# BioSignalPi-VersionA.net
KiCad netlist of a schematic drawn in EAGLE
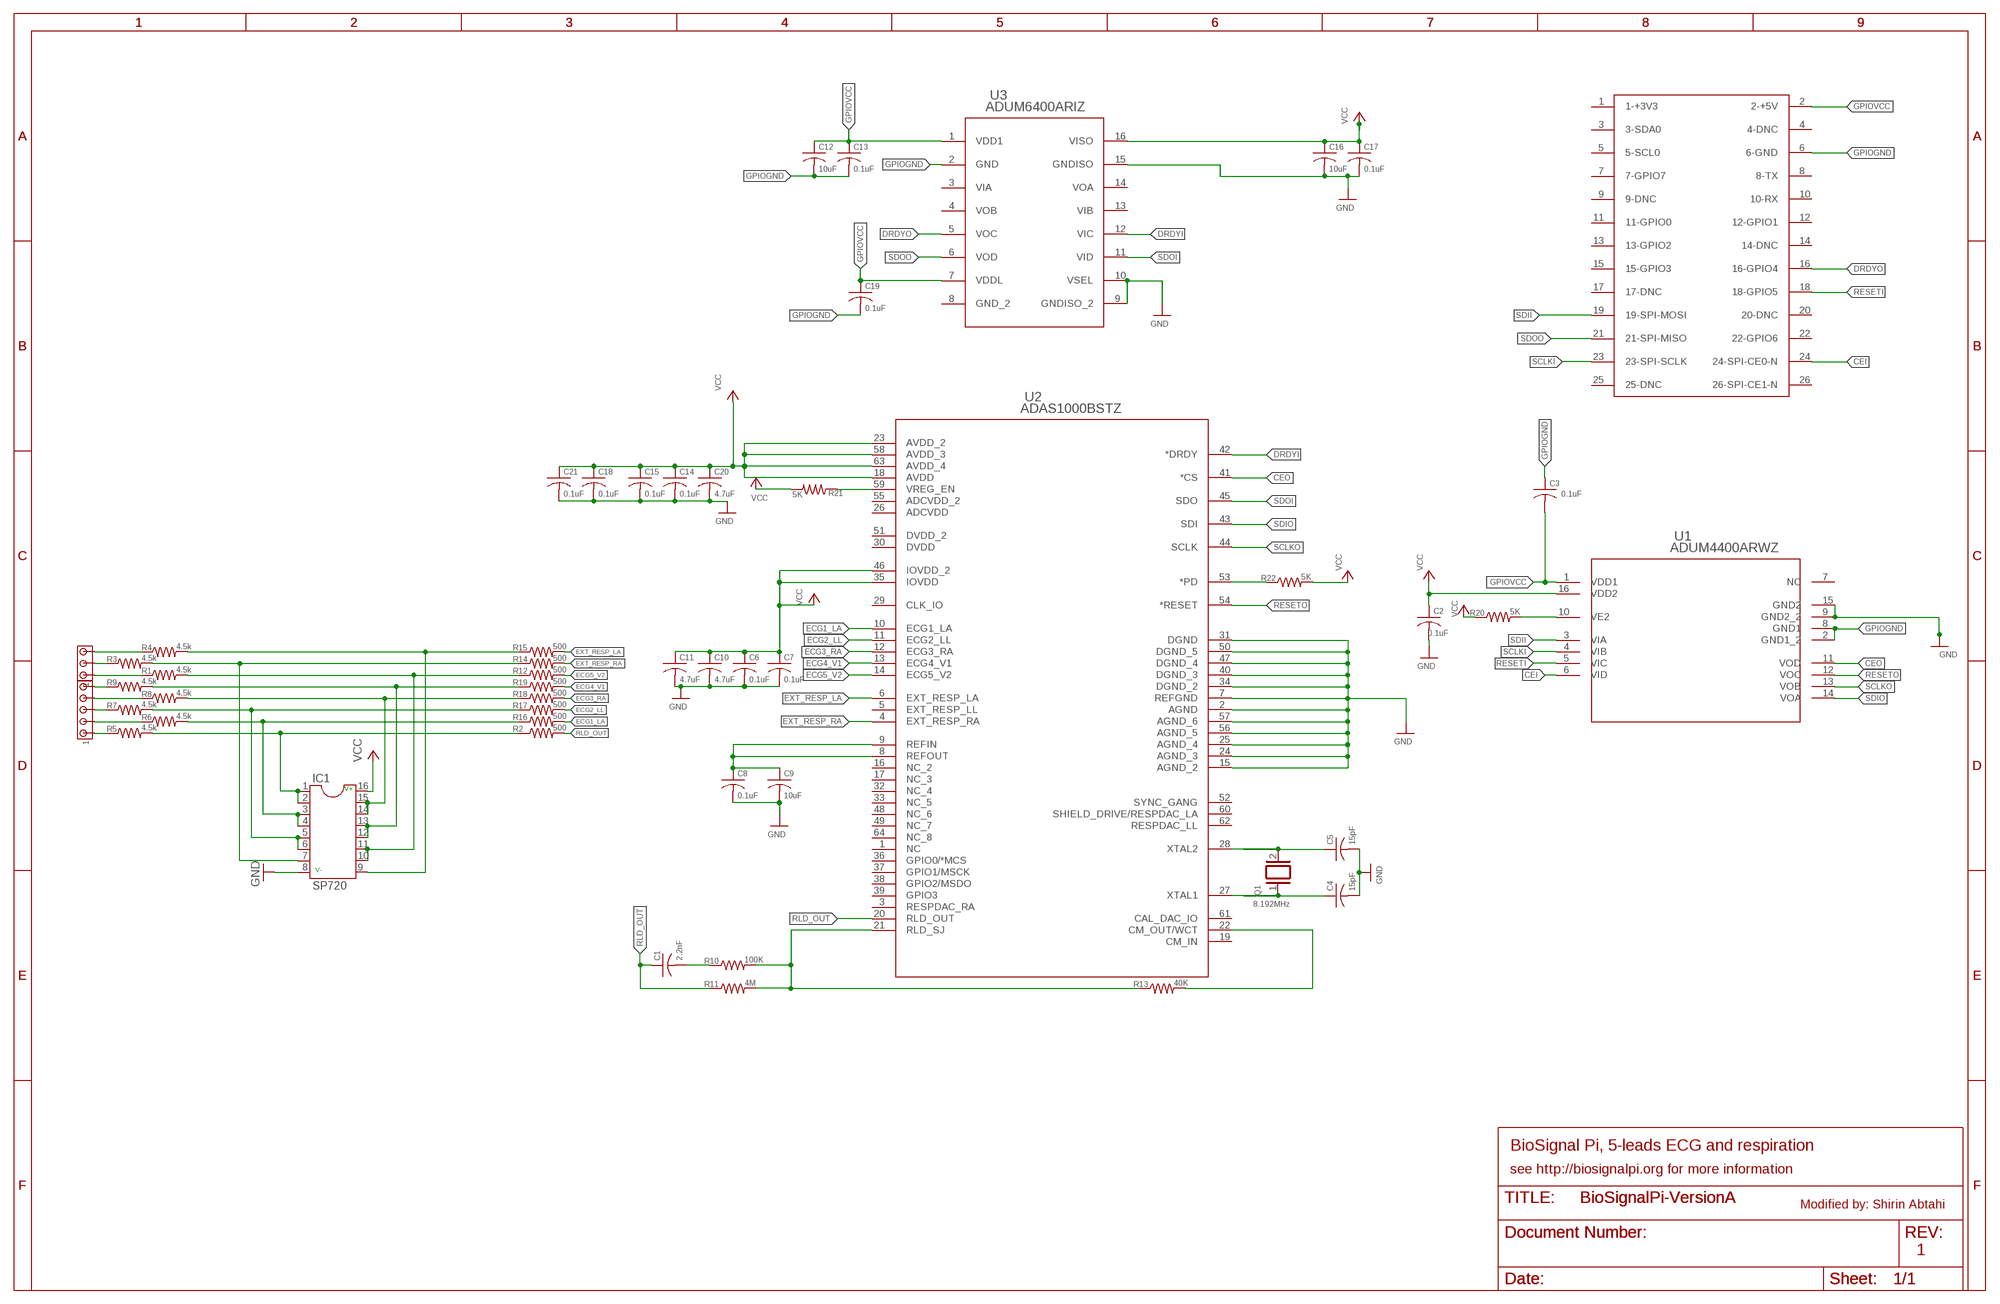
[diagram p0: schematic, sheet 1]

(export (version "E")
  (design (tool "Eeschema 10.0.6"))
  (components
    (comp (ref "C1")
      (value "2.2nF")
      (footprint "eagle-import:C0805")
      (libsource (lib "eagle-import") (part "C-USC0805"))
    )
    (comp (ref "C2")
      (value "0.1uF")
      (footprint "eagle-import:C0805")
      (libsource (lib "eagle-import") (part "C-USC0805"))
    )
    (comp (ref "C3")
      (value "0.1uF")
      (footprint "eagle-import:C0805")
      (libsource (lib "eagle-import") (part "C-USC0805"))
    )
    (comp (ref "C4")
      (value "15pF")
      (footprint "eagle-import:C0805")
      (libsource (lib "eagle-import") (part "C-USC0805"))
    )
    (comp (ref "C5")
      (value "15pF")
      (footprint "eagle-import:C0805")
      (libsource (lib "eagle-import") (part "C-USC0805"))
    )
    (comp (ref "C6")
      (value "0.1uF")
      (footprint "eagle-import:C0805")
      (libsource (lib "eagle-import") (part "C-USC0805"))
    )
    (comp (ref "C7")
      (value "0.1uF")
      (footprint "eagle-import:C0805")
      (libsource (lib "eagle-import") (part "C-USC0805"))
    )
    (comp (ref "C8")
      (value "0.1uF")
      (footprint "eagle-import:C0805")
      (libsource (lib "eagle-import") (part "C-USC0805"))
    )
    (comp (ref "C9")
      (value "10uF")
      (footprint "eagle-import:C0805")
      (libsource (lib "eagle-import") (part "C-USC0805"))
    )
    (comp (ref "C10")
      (value "4.7uF")
      (footprint "eagle-import:C0805")
      (libsource (lib "eagle-import") (part "C-USC0805"))
    )
    (comp (ref "C11")
      (value "4.7uF")
      (footprint "eagle-import:C0805")
      (libsource (lib "eagle-import") (part "C-USC0805"))
    )
    (comp (ref "C12")
      (value "10uF")
      (footprint "eagle-import:C0805")
      (libsource (lib "eagle-import") (part "C-USC0805"))
    )
    (comp (ref "C13")
      (value "0.1uF")
      (footprint "eagle-import:C0805")
      (libsource (lib "eagle-import") (part "C-USC0805"))
    )
    (comp (ref "C14")
      (value "0.1uF")
      (footprint "eagle-import:C0805")
      (libsource (lib "eagle-import") (part "C-USC0805"))
    )
    (comp (ref "C15")
      (value "0.1uF")
      (footprint "eagle-import:C0805")
      (libsource (lib "eagle-import") (part "C-USC0805"))
    )
    (comp (ref "C16")
      (value "10uF")
      (footprint "eagle-import:C0805")
      (libsource (lib "eagle-import") (part "C-USC0805"))
    )
    (comp (ref "C17")
      (value "0.1uF")
      (footprint "eagle-import:C0805")
      (libsource (lib "eagle-import") (part "C-USC0805"))
    )
    (comp (ref "C18")
      (value "0.1uF")
      (footprint "eagle-import:C0805")
      (libsource (lib "eagle-import") (part "C-USC0805"))
    )
    (comp (ref "C19")
      (value "0.1uF")
      (footprint "eagle-import:C0805")
      (libsource (lib "eagle-import") (part "C-USC0805"))
    )
    (comp (ref "C20")
      (value "4.7uF")
      (footprint "eagle-import:C0805")
      (libsource (lib "eagle-import") (part "C-USC0805"))
    )
    (comp (ref "C21")
      (value "0.1uF")
      (footprint "eagle-import:C0805")
      (libsource (lib "eagle-import") (part "C-USC0805"))
    )
    (comp (ref "IC1")
      (value "SP720")
      (footprint "eagle-import:DIL16")
      (libsource (lib "eagle-import") (part "DIL16"))
    )
    (comp (ref "J1")
      (value "JUMPERS")
      (footprint "eagle-import:10X03MTA")
      (libsource (lib "eagle-import") (part "MTA03-100"))
    )
    (comp (ref "J2")
      (value "JUMPERS")
      (footprint "eagle-import:10X05MTA")
      (libsource (lib "eagle-import") (part "MTA05-100"))
    )
    (comp (ref "Q1")
      (value "8.192MHz")
      (footprint "eagle-import:QS")
      (libsource (lib "eagle-import") (part "XTAL/S"))
    )
    (comp (ref "R1")
      (value "4.5k")
      (footprint "eagle-import:R0805")
      (libsource (lib "eagle-import") (part "R-US_R0805"))
    )
    (comp (ref "R2")
      (value "500")
      (footprint "eagle-import:R0805")
      (libsource (lib "eagle-import") (part "R-US_R0805"))
    )
    (comp (ref "R3")
      (value "4.5k")
      (footprint "eagle-import:R0805")
      (libsource (lib "eagle-import") (part "R-US_R0805"))
    )
    (comp (ref "R4")
      (value "4.5k")
      (footprint "eagle-import:R0805")
      (libsource (lib "eagle-import") (part "R-US_R0805"))
    )
    (comp (ref "R5")
      (value "4.5k")
      (footprint "eagle-import:R0805")
      (libsource (lib "eagle-import") (part "R-US_R0805"))
    )
    (comp (ref "R6")
      (value "4.5k")
      (footprint "eagle-import:R0805")
      (libsource (lib "eagle-import") (part "R-US_R0805"))
    )
    (comp (ref "R7")
      (value "4.5k")
      (footprint "eagle-import:R0805")
      (libsource (lib "eagle-import") (part "R-US_R0805"))
    )
    (comp (ref "R8")
      (value "4.5k")
      (footprint "eagle-import:R0805")
      (libsource (lib "eagle-import") (part "R-US_R0805"))
    )
    (comp (ref "R9")
      (value "4.5k")
      (footprint "eagle-import:R0805")
      (libsource (lib "eagle-import") (part "R-US_R0805"))
    )
    (comp (ref "R10")
      (value "100K")
      (footprint "eagle-import:R0805")
      (libsource (lib "eagle-import") (part "R-US_R0805"))
    )
    (comp (ref "R11")
      (value "4M")
      (footprint "eagle-import:R0805")
      (libsource (lib "eagle-import") (part "R-US_R0805"))
    )
    (comp (ref "R12")
      (value "500")
      (footprint "eagle-import:R0805")
      (libsource (lib "eagle-import") (part "R-US_R0805"))
    )
    (comp (ref "R13")
      (value "40K")
      (footprint "eagle-import:R0805")
      (libsource (lib "eagle-import") (part "R-US_R0805"))
    )
    (comp (ref "R14")
      (value "500")
      (footprint "eagle-import:R0805")
      (libsource (lib "eagle-import") (part "R-US_R0805"))
    )
    (comp (ref "R15")
      (value "500")
      (footprint "eagle-import:R0805")
      (libsource (lib "eagle-import") (part "R-US_R0805"))
    )
    (comp (ref "R16")
      (value "500")
      (footprint "eagle-import:R0805")
      (libsource (lib "eagle-import") (part "R-US_R0805"))
    )
    (comp (ref "R17")
      (value "500")
      (footprint "eagle-import:R0805")
      (libsource (lib "eagle-import") (part "R-US_R0805"))
    )
    (comp (ref "R18")
      (value "500")
      (footprint "eagle-import:R0805")
      (libsource (lib "eagle-import") (part "R-US_R0805"))
    )
    (comp (ref "R19")
      (value "500")
      (footprint "eagle-import:R0805")
      (libsource (lib "eagle-import") (part "R-US_R0805"))
    )
    (comp (ref "R20")
      (value "5K")
      (footprint "eagle-import:R0805")
      (libsource (lib "eagle-import") (part "R-US_R0805"))
    )
    (comp (ref "R21")
      (value "5K")
      (footprint "eagle-import:R0805")
      (libsource (lib "eagle-import") (part "R-US_R0805"))
    )
    (comp (ref "R22")
      (value "5K")
      (footprint "eagle-import:R0805")
      (libsource (lib "eagle-import") (part "R-US_R0805"))
    )
    (comp (ref "U$1")
      (value "RASPBERRY-PI")
      (footprint "eagle-import:RASPBERRY-PI")
      (libsource (lib "eagle-import") (part "RASPBERRY-PI"))
    )
    (comp (ref "U1")
      (value "ADUM4400ARWZ")
      (footprint "eagle-import:RW_16")
      (libsource (lib "eagle-import") (part "ADUM4400ARWZ"))
    )
    (comp (ref "U2")
      (value "ADAS1000BSTZ")
      (footprint "eagle-import:ST_64_2")
      (libsource (lib "eagle-import") (part "ADAS1000BSTZ"))
    )
    (comp (ref "U3")
      (value "ADUM6400ARIZ")
      (footprint "eagle-import:RI_16_1")
      (libsource (lib "eagle-import") (part "ADUM6400ARIZ"))
    )
  )
  (nets
    (net (code "1") (name "CEI") (class "Default")
      (node (ref "U$1") (pin "24") (pinfunction "24-SPI-CE0-N_24") (pintype "bidirectional"))
      (node (ref "U1") (pin "6") (pinfunction "VID_6") (pintype "passive"))
    )
    (net (code "2") (name "CEO") (class "Default")
      (node (ref "U1") (pin "11") (pinfunction "VOD_11") (pintype "passive"))
      (node (ref "U2") (pin "41") (pinfunction "*CS_41") (pintype "passive"))
    )
    (net (code "3") (name "DRDYI") (class "Default")
      (node (ref "U2") (pin "42") (pinfunction "*DRDY_42") (pintype "passive"))
      (node (ref "U3") (pin "12") (pinfunction "VIC_12") (pintype "passive"))
    )
    (net (code "4") (name "DRDYO") (class "Default")
      (node (ref "U$1") (pin "16") (pinfunction "16-GPIO4_16") (pintype "bidirectional"))
      (node (ref "U3") (pin "5") (pinfunction "VOC_5") (pintype "passive"))
    )
    (net (code "5") (name "ECG1_LA") (class "Default")
      (node (ref "R16") (pin "2") (pinfunction "2_2") (pintype "passive"))
      (node (ref "U2") (pin "10") (pinfunction "ECG1_LA_10") (pintype "passive"))
    )
    (net (code "6") (name "ECG2_LL") (class "Default")
      (node (ref "R17") (pin "2") (pinfunction "2_2") (pintype "passive"))
      (node (ref "U2") (pin "11") (pinfunction "ECG2_LL_11") (pintype "passive"))
    )
    (net (code "7") (name "ECG3_RA") (class "Default")
      (node (ref "R18") (pin "2") (pinfunction "2_2") (pintype "passive"))
      (node (ref "U2") (pin "12") (pinfunction "ECG3_RA_12") (pintype "passive"))
    )
    (net (code "8") (name "ECG4_V1") (class "Default")
      (node (ref "R19") (pin "2") (pinfunction "2_2") (pintype "passive"))
      (node (ref "U2") (pin "13") (pinfunction "ECG4_V1_13") (pintype "passive"))
    )
    (net (code "9") (name "ECG5_V2") (class "Default")
      (node (ref "R12") (pin "2") (pinfunction "2_2") (pintype "passive"))
      (node (ref "U2") (pin "14") (pinfunction "ECG5_V2_14") (pintype "passive"))
    )
    (net (code "10") (name "EXT_RESP_LA") (class "Default")
      (node (ref "R15") (pin "2") (pinfunction "2_2") (pintype "passive"))
      (node (ref "U2") (pin "6") (pinfunction "EXT_RESP_LA_6") (pintype "passive"))
    )
    (net (code "11") (name "EXT_RESP_RA") (class "Default")
      (node (ref "R14") (pin "2") (pinfunction "2_2") (pintype "passive"))
      (node (ref "U2") (pin "4") (pinfunction "EXT_RESP_RA_4") (pintype "passive"))
    )
    (net (code "12") (name "GND") (class "Default")
      (node (ref "C10") (pin "2") (pinfunction "2_2") (pintype "passive"))
      (node (ref "C11") (pin "2") (pinfunction "2_2") (pintype "passive"))
      (node (ref "C14") (pin "2") (pinfunction "2_2") (pintype "passive"))
      (node (ref "C15") (pin "2") (pinfunction "2_2") (pintype "passive"))
      (node (ref "C16") (pin "2") (pinfunction "2_2") (pintype "passive"))
      (node (ref "C17") (pin "2") (pinfunction "2_2") (pintype "passive"))
      (node (ref "C18") (pin "2") (pinfunction "2_2") (pintype "passive"))
      (node (ref "C2") (pin "2") (pinfunction "2_2") (pintype "passive"))
      (node (ref "C20") (pin "2") (pinfunction "2_2") (pintype "passive"))
      (node (ref "C21") (pin "2") (pinfunction "2_2") (pintype "passive"))
      (node (ref "C4") (pin "2") (pinfunction "2_2") (pintype "passive"))
      (node (ref "C5") (pin "2") (pinfunction "2_2") (pintype "passive"))
      (node (ref "C6") (pin "2") (pinfunction "2_2") (pintype "passive"))
      (node (ref "C7") (pin "2") (pinfunction "2_2") (pintype "passive"))
      (node (ref "C8") (pin "2") (pinfunction "2_2") (pintype "passive"))
      (node (ref "C9") (pin "2") (pinfunction "2_2") (pintype "passive"))
      (node (ref "IC1") (pin "8") (pinfunction "8_8") (pintype "passive"))
      (node (ref "U1") (pin "15") (pinfunction "GND2_15") (pintype "passive"))
      (node (ref "U1") (pin "9") (pinfunction "GND2_2_9") (pintype "passive"))
      (node (ref "U2") (pin "15") (pinfunction "AGND_2_15") (pintype "passive"))
      (node (ref "U2") (pin "2") (pinfunction "AGND_2") (pintype "passive"))
      (node (ref "U2") (pin "24") (pinfunction "AGND_3_24") (pintype "passive"))
      (node (ref "U2") (pin "25") (pinfunction "AGND_4_25") (pintype "passive"))
      (node (ref "U2") (pin "31") (pinfunction "DGND_31") (pintype "passive"))
      (node (ref "U2") (pin "34") (pinfunction "DGND_2_34") (pintype "passive"))
      (node (ref "U2") (pin "40") (pinfunction "DGND_3_40") (pintype "passive"))
      (node (ref "U2") (pin "47") (pinfunction "DGND_4_47") (pintype "passive"))
      (node (ref "U2") (pin "50") (pinfunction "DGND_5_50") (pintype "passive"))
      (node (ref "U2") (pin "56") (pinfunction "AGND_5_56") (pintype "passive"))
      (node (ref "U2") (pin "57") (pinfunction "AGND_6_57") (pintype "passive"))
      (node (ref "U2") (pin "7") (pinfunction "REFGND_7") (pintype "passive"))
      (node (ref "U3") (pin "10") (pinfunction "VSEL_10") (pintype "passive"))
      (node (ref "U3") (pin "15") (pinfunction "GNDISO_15") (pintype "passive"))
      (node (ref "U3") (pin "9") (pinfunction "GNDISO_2_9") (pintype "passive"))
    )
    (net (code "13") (name "GPIOGND") (class "Default")
      (node (ref "C12") (pin "2") (pinfunction "2_2") (pintype "passive"))
      (node (ref "C13") (pin "2") (pinfunction "2_2") (pintype "passive"))
      (node (ref "C19") (pin "2") (pinfunction "2_2") (pintype "passive"))
      (node (ref "C3") (pin "1") (pinfunction "1_1") (pintype "passive"))
      (node (ref "U$1") (pin "6") (pinfunction "6-GND_6") (pintype "bidirectional"))
      (node (ref "U1") (pin "2") (pinfunction "GND1_2_2") (pintype "passive"))
      (node (ref "U1") (pin "8") (pinfunction "GND1_8") (pintype "passive"))
      (node (ref "U3") (pin "2") (pinfunction "GND_2") (pintype "passive"))
    )
    (net (code "14") (name "GPIOVCC") (class "Default")
      (node (ref "C12") (pin "1") (pinfunction "1_1") (pintype "passive"))
      (node (ref "C13") (pin "1") (pinfunction "1_1") (pintype "passive"))
      (node (ref "C19") (pin "1") (pinfunction "1_1") (pintype "passive"))
      (node (ref "C3") (pin "2") (pinfunction "2_2") (pintype "passive"))
      (node (ref "U$1") (pin "2") (pinfunction "2-+5V_2") (pintype "bidirectional"))
      (node (ref "U1") (pin "1") (pinfunction "VDD1_1") (pintype "passive"))
      (node (ref "U3") (pin "1") (pinfunction "VDD1_1") (pintype "passive"))
      (node (ref "U3") (pin "7") (pinfunction "VDDL_7") (pintype "passive"))
    )
    (net (code "15") (name "Net-(C1-Pad2)") (class "Default")
      (node (ref "C1") (pin "2") (pinfunction "2_2") (pintype "passive"))
      (node (ref "R10") (pin "1") (pinfunction "1_1") (pintype "passive"))
    )
    (net (code "16") (name "Net-(IC1-Pad1)") (class "Default")
      (node (ref "IC1") (pin "1") (pinfunction "1_1") (pintype "passive"))
      (node (ref "IC1") (pin "2") (pinfunction "2_2") (pintype "passive"))
      (node (ref "R2") (pin "1") (pinfunction "1_1") (pintype "passive"))
      (node (ref "R5") (pin "2") (pinfunction "2_2") (pintype "passive"))
    )
    (net (code "17") (name "Net-(IC1-Pad3)") (class "Default")
      (node (ref "IC1") (pin "3") (pinfunction "3_3") (pintype "passive"))
      (node (ref "IC1") (pin "4") (pinfunction "4_4") (pintype "passive"))
      (node (ref "R16") (pin "1") (pinfunction "1_1") (pintype "passive"))
      (node (ref "R6") (pin "2") (pinfunction "2_2") (pintype "passive"))
    )
    (net (code "18") (name "Net-(IC1-Pad5)") (class "Default")
      (node (ref "IC1") (pin "5") (pinfunction "5_5") (pintype "passive"))
      (node (ref "IC1") (pin "6") (pinfunction "6_6") (pintype "passive"))
      (node (ref "R17") (pin "1") (pinfunction "1_1") (pintype "passive"))
      (node (ref "R7") (pin "2") (pinfunction "2_2") (pintype "passive"))
    )
    (net (code "19") (name "Net-(IC1-Pad7)") (class "Default")
      (node (ref "IC1") (pin "7") (pinfunction "7_7") (pintype "passive"))
      (node (ref "R14") (pin "1") (pinfunction "1_1") (pintype "passive"))
      (node (ref "R3") (pin "2") (pinfunction "2_2") (pintype "passive"))
    )
    (net (code "20") (name "Net-(IC1-Pad9)") (class "Default")
      (node (ref "IC1") (pin "9") (pinfunction "9_9") (pintype "passive"))
      (node (ref "R15") (pin "1") (pinfunction "1_1") (pintype "passive"))
      (node (ref "R4") (pin "2") (pinfunction "2_2") (pintype "passive"))
    )
    (net (code "21") (name "Net-(IC1-Pad10)") (class "Default")
      (node (ref "IC1") (pin "10") (pinfunction "10_10") (pintype "passive"))
      (node (ref "IC1") (pin "11") (pinfunction "11_11") (pintype "passive"))
      (node (ref "R1") (pin "2") (pinfunction "2_2") (pintype "passive"))
      (node (ref "R12") (pin "1") (pinfunction "1_1") (pintype "passive"))
    )
    (net (code "22") (name "Net-(IC1-Pad12)") (class "Default")
      (node (ref "IC1") (pin "12") (pinfunction "12_12") (pintype "passive"))
      (node (ref "IC1") (pin "13") (pinfunction "13_13") (pintype "passive"))
      (node (ref "R19") (pin "1") (pinfunction "1_1") (pintype "passive"))
      (node (ref "R9") (pin "2") (pinfunction "2_2") (pintype "passive"))
    )
    (net (code "23") (name "Net-(IC1-Pad14)") (class "Default")
      (node (ref "IC1") (pin "14") (pinfunction "14_14") (pintype "passive"))
      (node (ref "IC1") (pin "15") (pinfunction "15_15") (pintype "passive"))
      (node (ref "R18") (pin "1") (pinfunction "1_1") (pintype "passive"))
      (node (ref "R8") (pin "2") (pinfunction "2_2") (pintype "passive"))
    )
    (net (code "24") (name "Net-(J1-Pad1)") (class "Default")
      (node (ref "J1") (pin "1") (pinfunction "1_1") (pintype "passive"))
      (node (ref "R1") (pin "1") (pinfunction "1_1") (pintype "passive"))
    )
    (net (code "25") (name "Net-(J1-Pad2)") (class "Default")
      (node (ref "J1") (pin "2") (pinfunction "2_2") (pintype "passive"))
      (node (ref "R3") (pin "1") (pinfunction "1_1") (pintype "passive"))
    )
    (net (code "26") (name "Net-(J1-Pad3)") (class "Default")
      (node (ref "J1") (pin "3") (pinfunction "3_3") (pintype "passive"))
      (node (ref "R4") (pin "1") (pinfunction "1_1") (pintype "passive"))
    )
    (net (code "27") (name "Net-(J2-Pad1)") (class "Default")
      (node (ref "J2") (pin "1") (pinfunction "1_1") (pintype "passive"))
      (node (ref "R5") (pin "1") (pinfunction "1_1") (pintype "passive"))
    )
    (net (code "28") (name "Net-(J2-Pad2)") (class "Default")
      (node (ref "J2") (pin "2") (pinfunction "2_2") (pintype "passive"))
      (node (ref "R6") (pin "1") (pinfunction "1_1") (pintype "passive"))
    )
    (net (code "29") (name "Net-(J2-Pad3)") (class "Default")
      (node (ref "J2") (pin "3") (pinfunction "3_3") (pintype "passive"))
      (node (ref "R7") (pin "1") (pinfunction "1_1") (pintype "passive"))
    )
    (net (code "30") (name "Net-(J2-Pad4)") (class "Default")
      (node (ref "J2") (pin "4") (pinfunction "4_4") (pintype "passive"))
      (node (ref "R8") (pin "1") (pinfunction "1_1") (pintype "passive"))
    )
    (net (code "31") (name "Net-(J2-Pad5)") (class "Default")
      (node (ref "J2") (pin "5") (pinfunction "5_5") (pintype "passive"))
      (node (ref "R9") (pin "1") (pinfunction "1_1") (pintype "passive"))
    )
    (net (code "32") (name "Net-(U1-VE2)") (class "Default")
      (node (ref "R20") (pin "2") (pinfunction "2_2") (pintype "passive"))
      (node (ref "U1") (pin "10") (pinfunction "VE2_10") (pintype "passive"))
    )
    (net (code "33") (name "Net-(U2-*PD)") (class "Default")
      (node (ref "R22") (pin "1") (pinfunction "1_1") (pintype "passive"))
      (node (ref "U2") (pin "53") (pinfunction "*PD_53") (pintype "passive"))
    )
    (net (code "34") (name "Net-(U2-CM_OUT{slash}WCT)") (class "Default")
      (node (ref "R13") (pin "2") (pinfunction "2_2") (pintype "passive"))
      (node (ref "U2") (pin "22") (pinfunction "CM_OUT/WCT_22") (pintype "passive"))
    )
    (net (code "35") (name "Net-(U2-REFIN)") (class "Default")
      (node (ref "C8") (pin "1") (pinfunction "1_1") (pintype "passive"))
      (node (ref "C9") (pin "1") (pinfunction "1_1") (pintype "passive"))
      (node (ref "U2") (pin "8") (pinfunction "REFOUT_8") (pintype "passive"))
      (node (ref "U2") (pin "9") (pinfunction "REFIN_9") (pintype "passive"))
    )
    (net (code "36") (name "Net-(U2-RLD_SJ)") (class "Default")
      (node (ref "R10") (pin "2") (pinfunction "2_2") (pintype "passive"))
      (node (ref "R11") (pin "2") (pinfunction "2_2") (pintype "passive"))
      (node (ref "R13") (pin "1") (pinfunction "1_1") (pintype "passive"))
      (node (ref "U2") (pin "21") (pinfunction "RLD_SJ_21") (pintype "passive"))
    )
    (net (code "37") (name "Net-(U2-VREG_EN)") (class "Default")
      (node (ref "R21") (pin "1") (pinfunction "1_1") (pintype "passive"))
      (node (ref "U2") (pin "59") (pinfunction "VREG_EN_59") (pintype "passive"))
    )
    (net (code "38") (name "Net-(U2-XTAL1)") (class "Default")
      (node (ref "C4") (pin "1") (pinfunction "1_1") (pintype "passive"))
      (node (ref "Q1") (pin "1") (pinfunction "1_1") (pintype "passive"))
      (node (ref "U2") (pin "27") (pinfunction "XTAL1_27") (pintype "passive"))
    )
    (net (code "39") (name "Net-(U2-XTAL2)") (class "Default")
      (node (ref "C5") (pin "1") (pinfunction "1_1") (pintype "passive"))
      (node (ref "Q1") (pin "2") (pinfunction "2_2") (pintype "passive"))
      (node (ref "U2") (pin "28") (pinfunction "XTAL2_28") (pintype "passive"))
    )
    (net (code "40") (name "RESETI") (class "Default")
      (node (ref "U$1") (pin "18") (pinfunction "18-GPIO5_18") (pintype "bidirectional"))
      (node (ref "U1") (pin "5") (pinfunction "VIC_5") (pintype "passive"))
    )
    (net (code "41") (name "RESETO") (class "Default")
      (node (ref "U1") (pin "12") (pinfunction "VOC_12") (pintype "passive"))
      (node (ref "U2") (pin "54") (pinfunction "*RESET_54") (pintype "passive"))
    )
    (net (code "42") (name "RLD_OUT") (class "Default")
      (node (ref "C1") (pin "1") (pinfunction "1_1") (pintype "passive"))
      (node (ref "R11") (pin "1") (pinfunction "1_1") (pintype "passive"))
      (node (ref "R2") (pin "2") (pinfunction "2_2") (pintype "passive"))
      (node (ref "U2") (pin "20") (pinfunction "RLD_OUT_20") (pintype "passive"))
    )
    (net (code "43") (name "SCLKI") (class "Default")
      (node (ref "U$1") (pin "23") (pinfunction "23-SPI-SCLK_23") (pintype "bidirectional"))
      (node (ref "U1") (pin "4") (pinfunction "VIB_4") (pintype "passive"))
    )
    (net (code "44") (name "SCLKO") (class "Default")
      (node (ref "U1") (pin "13") (pinfunction "VOB_13") (pintype "passive"))
      (node (ref "U2") (pin "44") (pinfunction "SCLK_44") (pintype "passive"))
    )
    (net (code "45") (name "SDII") (class "Default")
      (node (ref "U$1") (pin "19") (pinfunction "19-SPI-MOSI_19") (pintype "bidirectional"))
      (node (ref "U1") (pin "3") (pinfunction "VIA_3") (pintype "passive"))
    )
    (net (code "46") (name "SDIO") (class "Default")
      (node (ref "U1") (pin "14") (pinfunction "VOA_14") (pintype "passive"))
      (node (ref "U2") (pin "43") (pinfunction "SDI_43") (pintype "passive"))
    )
    (net (code "47") (name "SDOI") (class "Default")
      (node (ref "U2") (pin "45") (pinfunction "SDO_45") (pintype "passive"))
      (node (ref "U3") (pin "11") (pinfunction "VID_11") (pintype "passive"))
    )
    (net (code "48") (name "SDOO") (class "Default")
      (node (ref "U$1") (pin "21") (pinfunction "21-SPI-MISO_21") (pintype "bidirectional"))
      (node (ref "U3") (pin "6") (pinfunction "VOD_6") (pintype "passive"))
    )
    (net (code "49") (name "VCC") (class "Default")
      (node (ref "C10") (pin "1") (pinfunction "1_1") (pintype "passive"))
      (node (ref "C11") (pin "1") (pinfunction "1_1") (pintype "passive"))
      (node (ref "C14") (pin "1") (pinfunction "1_1") (pintype "passive"))
      (node (ref "C15") (pin "1") (pinfunction "1_1") (pintype "passive"))
      (node (ref "C16") (pin "1") (pinfunction "1_1") (pintype "passive"))
      (node (ref "C17") (pin "1") (pinfunction "1_1") (pintype "passive"))
      (node (ref "C18") (pin "1") (pinfunction "1_1") (pintype "passive"))
      (node (ref "C2") (pin "1") (pinfunction "1_1") (pintype "passive"))
      (node (ref "C20") (pin "1") (pinfunction "1_1") (pintype "passive"))
      (node (ref "C21") (pin "1") (pinfunction "1_1") (pintype "passive"))
      (node (ref "C6") (pin "1") (pinfunction "1_1") (pintype "passive"))
      (node (ref "C7") (pin "1") (pinfunction "1_1") (pintype "passive"))
      (node (ref "IC1") (pin "16") (pinfunction "16_16") (pintype "passive"))
      (node (ref "R20") (pin "1") (pinfunction "1_1") (pintype "passive"))
      (node (ref "R21") (pin "2") (pinfunction "2_2") (pintype "passive"))
      (node (ref "R22") (pin "2") (pinfunction "2_2") (pintype "passive"))
      (node (ref "U1") (pin "16") (pinfunction "VDD2_16") (pintype "passive"))
      (node (ref "U2") (pin "18") (pinfunction "AVDD_18") (pintype "passive"))
      (node (ref "U2") (pin "23") (pinfunction "AVDD_2_23") (pintype "passive"))
      (node (ref "U2") (pin "35") (pinfunction "IOVDD_35") (pintype "passive"))
      (node (ref "U2") (pin "46") (pinfunction "IOVDD_2_46") (pintype "passive"))
      (node (ref "U2") (pin "58") (pinfunction "AVDD_3_58") (pintype "passive"))
      (node (ref "U2") (pin "63") (pinfunction "AVDD_4_63") (pintype "passive"))
      (node (ref "U3") (pin "16") (pinfunction "VISO_16") (pintype "passive"))
    )
    (net (code "50") (name "unconnected-(U$1-1-+3V3-Pad1)") (class "Default")
      (node (ref "U$1") (pin "1") (pinfunction "1-+3V3_1") (pintype "bidirectional"))
    )
    (net (code "51") (name "unconnected-(U$1-3-SDA0-Pad3)") (class "Default")
      (node (ref "U$1") (pin "3") (pinfunction "3-SDA0_3") (pintype "bidirectional"))
    )
    (net (code "52") (name "unconnected-(U$1-4-DNC-Pad4)") (class "Default")
      (node (ref "U$1") (pin "4") (pinfunction "4-DNC_4") (pintype "bidirectional"))
    )
    (net (code "53") (name "unconnected-(U$1-5-SCL0-Pad5)") (class "Default")
      (node (ref "U$1") (pin "5") (pinfunction "5-SCL0_5") (pintype "bidirectional"))
    )
    (net (code "54") (name "unconnected-(U$1-7-GPIO7-Pad7)") (class "Default")
      (node (ref "U$1") (pin "7") (pinfunction "7-GPIO7_7") (pintype "bidirectional"))
    )
    (net (code "55") (name "unconnected-(U$1-8-TX-Pad8)") (class "Default")
      (node (ref "U$1") (pin "8") (pinfunction "8-TX_8") (pintype "bidirectional"))
    )
    (net (code "56") (name "unconnected-(U$1-9-DNC-Pad9)") (class "Default")
      (node (ref "U$1") (pin "9") (pinfunction "9-DNC_9") (pintype "bidirectional"))
    )
    (net (code "57") (name "unconnected-(U$1-10-RX-Pad10)") (class "Default")
      (node (ref "U$1") (pin "10") (pinfunction "10-RX_10") (pintype "bidirectional"))
    )
    (net (code "58") (name "unconnected-(U$1-11-GPIO0-Pad11)") (class "Default")
      (node (ref "U$1") (pin "11") (pinfunction "11-GPIO0_11") (pintype "bidirectional"))
    )
    (net (code "59") (name "unconnected-(U$1-12-GPIO1-Pad12)") (class "Default")
      (node (ref "U$1") (pin "12") (pinfunction "12-GPIO1_12") (pintype "bidirectional"))
    )
    (net (code "60") (name "unconnected-(U$1-13-GPIO2-Pad13)") (class "Default")
      (node (ref "U$1") (pin "13") (pinfunction "13-GPIO2_13") (pintype "bidirectional"))
    )
    (net (code "61") (name "unconnected-(U$1-14-DNC-Pad14)") (class "Default")
      (node (ref "U$1") (pin "14") (pinfunction "14-DNC_14") (pintype "bidirectional"))
    )
    (net (code "62") (name "unconnected-(U$1-15-GPIO3-Pad15)") (class "Default")
      (node (ref "U$1") (pin "15") (pinfunction "15-GPIO3_15") (pintype "bidirectional"))
    )
    (net (code "63") (name "unconnected-(U$1-17-DNC-Pad17)") (class "Default")
      (node (ref "U$1") (pin "17") (pinfunction "17-DNC_17") (pintype "bidirectional"))
    )
    (net (code "64") (name "unconnected-(U$1-20-DNC-Pad20)") (class "Default")
      (node (ref "U$1") (pin "20") (pinfunction "20-DNC_20") (pintype "bidirectional"))
    )
    (net (code "65") (name "unconnected-(U$1-22-GPIO6-Pad22)") (class "Default")
      (node (ref "U$1") (pin "22") (pinfunction "22-GPIO6_22") (pintype "bidirectional"))
    )
    (net (code "66") (name "unconnected-(U$1-25-DNC-Pad25)") (class "Default")
      (node (ref "U$1") (pin "25") (pinfunction "25-DNC_25") (pintype "bidirectional"))
    )
    (net (code "67") (name "unconnected-(U$1-26-SPI-CE1-N-Pad26)") (class "Default")
      (node (ref "U$1") (pin "26") (pinfunction "26-SPI-CE1-N_26") (pintype "bidirectional"))
    )
    (net (code "68") (name "unconnected-(U1-NC-Pad7)") (class "Default")
      (node (ref "U1") (pin "7") (pinfunction "NC_7") (pintype "passive"))
    )
    (net (code "69") (name "unconnected-(U2-ADCVDD-Pad26)") (class "Default")
      (node (ref "U2") (pin "26") (pinfunction "ADCVDD_26") (pintype "passive"))
    )
    (net (code "70") (name "unconnected-(U2-ADCVDD_2-Pad55)") (class "Default")
      (node (ref "U2") (pin "55") (pinfunction "ADCVDD_2_55") (pintype "passive"))
    )
    (net (code "71") (name "unconnected-(U2-CAL_DAC_IO-Pad61)") (class "Default")
      (node (ref "U2") (pin "61") (pinfunction "CAL_DAC_IO_61") (pintype "passive"))
    )
    (net (code "72") (name "unconnected-(U2-CLK_IO-Pad29)") (class "Default")
      (node (ref "U2") (pin "29") (pinfunction "CLK_IO_29") (pintype "passive"))
    )
    (net (code "73") (name "unconnected-(U2-CM_IN-Pad19)") (class "Default")
      (node (ref "U2") (pin "19") (pinfunction "CM_IN_19") (pintype "passive"))
    )
    (net (code "74") (name "unconnected-(U2-DVDD-Pad30)") (class "Default")
      (node (ref "U2") (pin "30") (pinfunction "DVDD_30") (pintype "passive"))
    )
    (net (code "75") (name "unconnected-(U2-DVDD_2-Pad51)") (class "Default")
      (node (ref "U2") (pin "51") (pinfunction "DVDD_2_51") (pintype "passive"))
    )
    (net (code "76") (name "unconnected-(U2-EXT_RESP_LL-Pad5)") (class "Default")
      (node (ref "U2") (pin "5") (pinfunction "EXT_RESP_LL_5") (pintype "passive"))
    )
    (net (code "77") (name "unconnected-(U2-GPIO0{slash}*MCS-Pad36)") (class "Default")
      (node (ref "U2") (pin "36") (pinfunction "GPIO0/*MCS_36") (pintype "passive"))
    )
    (net (code "78") (name "unconnected-(U2-GPIO1{slash}MSCK-Pad37)") (class "Default")
      (node (ref "U2") (pin "37") (pinfunction "GPIO1/MSCK_37") (pintype "passive"))
    )
    (net (code "79") (name "unconnected-(U2-GPIO2{slash}MSDO-Pad38)") (class "Default")
      (node (ref "U2") (pin "38") (pinfunction "GPIO2/MSDO_38") (pintype "passive"))
    )
    (net (code "80") (name "unconnected-(U2-GPIO3-Pad39)") (class "Default")
      (node (ref "U2") (pin "39") (pinfunction "GPIO3_39") (pintype "passive"))
    )
    (net (code "81") (name "unconnected-(U2-NC-Pad1)") (class "Default")
      (node (ref "U2") (pin "1") (pinfunction "NC_1") (pintype "passive"))
    )
    (net (code "82") (name "unconnected-(U2-NC_2-Pad16)") (class "Default")
      (node (ref "U2") (pin "16") (pinfunction "NC_2_16") (pintype "passive"))
    )
    (net (code "83") (name "unconnected-(U2-NC_3-Pad17)") (class "Default")
      (node (ref "U2") (pin "17") (pinfunction "NC_3_17") (pintype "passive"))
    )
    (net (code "84") (name "unconnected-(U2-NC_4-Pad32)") (class "Default")
      (node (ref "U2") (pin "32") (pinfunction "NC_4_32") (pintype "passive"))
    )
    (net (code "85") (name "unconnected-(U2-NC_5-Pad33)") (class "Default")
      (node (ref "U2") (pin "33") (pinfunction "NC_5_33") (pintype "passive"))
    )
    (net (code "86") (name "unconnected-(U2-NC_6-Pad48)") (class "Default")
      (node (ref "U2") (pin "48") (pinfunction "NC_6_48") (pintype "passive"))
    )
    (net (code "87") (name "unconnected-(U2-NC_7-Pad49)") (class "Default")
      (node (ref "U2") (pin "49") (pinfunction "NC_7_49") (pintype "passive"))
    )
    (net (code "88") (name "unconnected-(U2-NC_8-Pad64)") (class "Default")
      (node (ref "U2") (pin "64") (pinfunction "NC_8_64") (pintype "passive"))
    )
    (net (code "89") (name "unconnected-(U2-RESPDAC_LL-Pad62)") (class "Default")
      (node (ref "U2") (pin "62") (pinfunction "RESPDAC_LL_62") (pintype "passive"))
    )
    (net (code "90") (name "unconnected-(U2-RESPDAC_RA-Pad3)") (class "Default")
      (node (ref "U2") (pin "3") (pinfunction "RESPDAC_RA_3") (pintype "passive"))
    )
    (net (code "91") (name "unconnected-(U2-SHIELD_DRIVE{slash}RESPDAC_LA-Pad60)") (class "Default")
      (node (ref "U2") (pin "60") (pinfunction "SHIELD_DRIVE/RESPDAC_LA_60") (pintype "passive"))
    )
    (net (code "92") (name "unconnected-(U2-SYNC_GANG-Pad52)") (class "Default")
      (node (ref "U2") (pin "52") (pinfunction "SYNC_GANG_52") (pintype "passive"))
    )
    (net (code "93") (name "unconnected-(U3-GND_2-Pad8)") (class "Default")
      (node (ref "U3") (pin "8") (pinfunction "GND_2_8") (pintype "passive"))
    )
    (net (code "94") (name "unconnected-(U3-VIA-Pad3)") (class "Default")
      (node (ref "U3") (pin "3") (pinfunction "VIA_3") (pintype "passive"))
    )
    (net (code "95") (name "unconnected-(U3-VIB-Pad13)") (class "Default")
      (node (ref "U3") (pin "13") (pinfunction "VIB_13") (pintype "passive"))
    )
    (net (code "96") (name "unconnected-(U3-VOA-Pad14)") (class "Default")
      (node (ref "U3") (pin "14") (pinfunction "VOA_14") (pintype "passive"))
    )
    (net (code "97") (name "unconnected-(U3-VOB-Pad4)") (class "Default")
      (node (ref "U3") (pin "4") (pinfunction "VOB_4") (pintype "passive"))
    )
  )
)
